# Microcontroller.net
KiCad netlist of a schematic drawn in Altium Designer
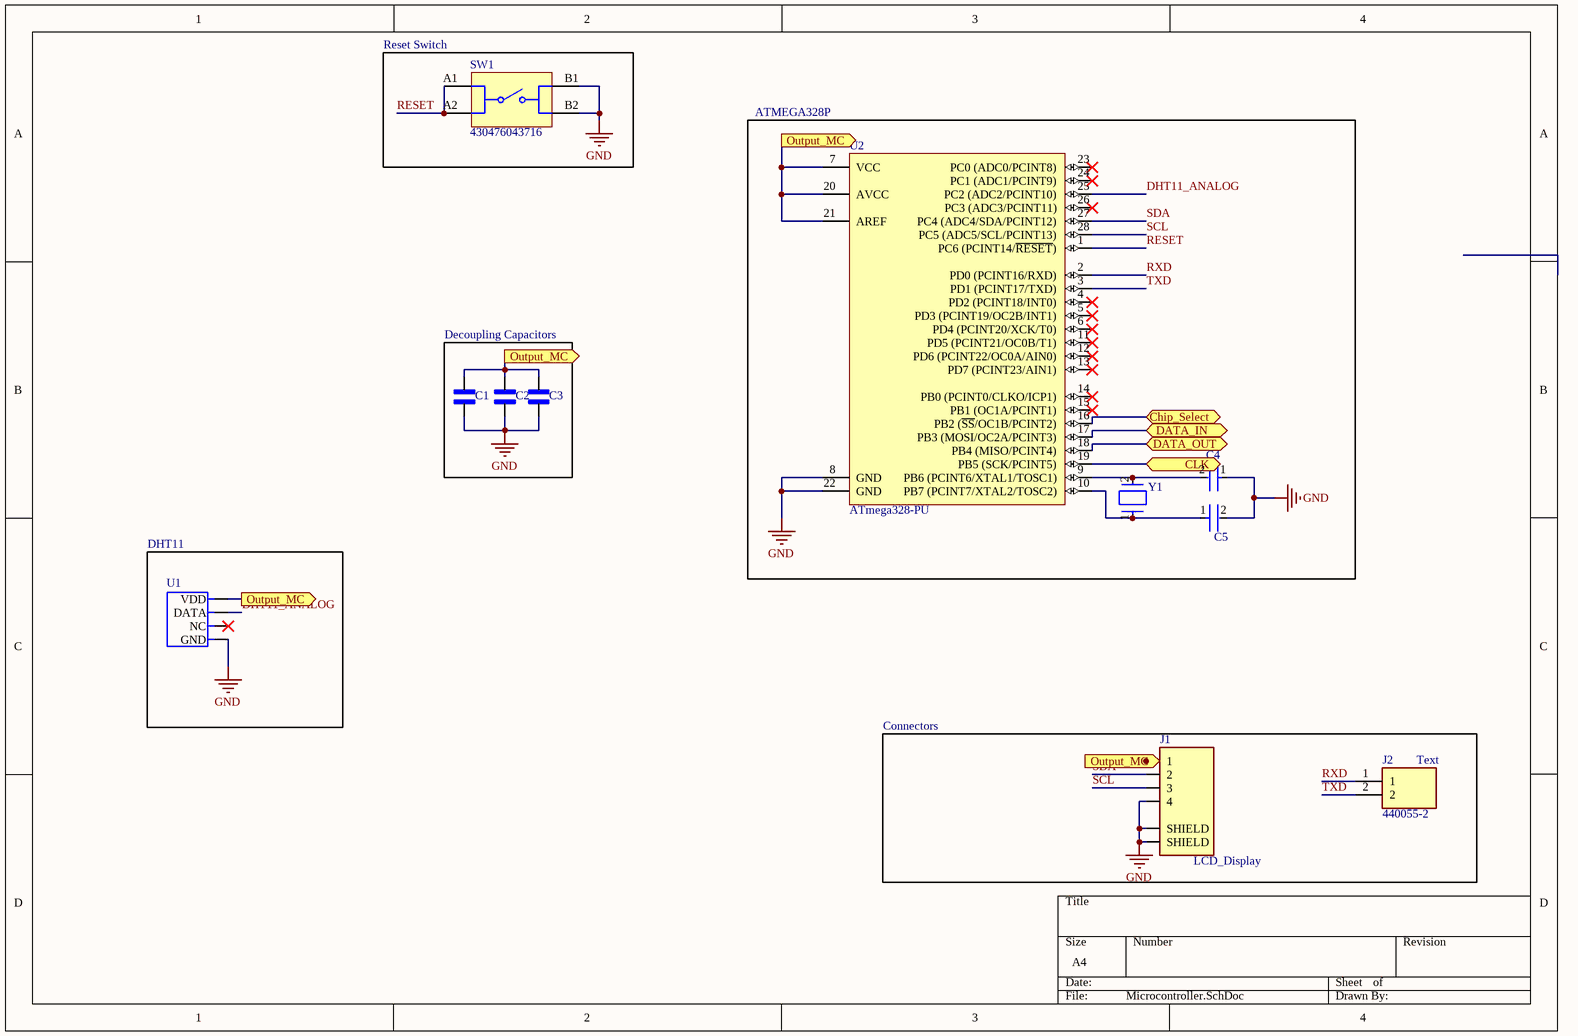
[diagram p0: Microcontroller.SchDoc]

(export (version "E")
  (design (tool "Eeschema 10.0.6"))
  (components
    (comp (ref "C1")
      (value "GRM033C71C104ME14D")
      (footprint "CAPC0603X33N")
      (description "Cap Ceramic 0.1uF 16V X7S 20% Pad SMD 0201 125C T/R")
      (fields (field (name "MF") "{'manufacturer': u'Murata'}"))
      (libsource (lib "SnapEDA_Library") (part "GRM033C71C104ME14D"))
    )
    (comp (ref "C2")
      (value "GRM033C71C104ME14D")
      (footprint "CAPC0603X33N")
      (description "Cap Ceramic 0.1uF 16V X7S 20% Pad SMD 0201 125C T/R")
      (fields (field (name "MF") "{'manufacturer': u'Murata'}"))
      (libsource (lib "SnapEDA_Library") (part "GRM033C71C104ME14D"))
    )
    (comp (ref "C3")
      (value "GRM033C71C104ME14D")
      (footprint "CAPC0603X33N")
      (description "Cap Ceramic 0.1uF 16V X7S 20% Pad SMD 0201 125C T/R")
      (fields (field (name "MF") "{'manufacturer': u'Murata'}"))
      (libsource (lib "SnapEDA_Library") (part "GRM033C71C104ME14D"))
    )
    (comp (ref "C4")
      (value "C0603X104K5RACTU")
      (footprint "FP-C0603-CJ-MFG")
      (description "CAP CER 0.1UF 50V X7R 0603")
      (fields (field (name "VOLTAGE") "50V") (field (name "MANUFACTURER") "Kemet"))
      (libsource (lib "Altium Content Vault") (part "11868f565c42a9108669ba33697ecf6"))
    )
    (comp (ref "C5")
      (value "C0603X104K5RACTU")
      (footprint "FP-C0603-CJ-MFG")
      (description "CAP CER 0.1UF 50V X7R 0603")
      (fields (field (name "VOLTAGE") "50V") (field (name "MANUFACTURER") "Kemet"))
      (libsource (lib "Altium Content Vault") (part "11868f565c42a9108669ba33697ecf6"))
    )
    (comp (ref "J1")
      (value "SM04B-SRSS-TB(LF)(SN)")
      (footprint "JST_SM04B-SRSS-TB(LF)(SN)")
      (description "SH Series 1.0 mm Pitch 2 Position Single Row Side Entry Shrouded Header")
      (fields (field (name "MF") "{'manufacturer': u'JST Sales'}"))
      (libsource (lib "SnapEDA_Library") (part "SM04B-SRSS-TB(LF)(SN)"))
    )
    (comp (ref "J2")
      (value "440055-2")
      (footprint "TE_440055-2")
      (fields (field (name "MF") "{'manufacturer': u'TE Connectivity'}"))
      (libsource (lib "SnapEDA_Library") (part "440055-2"))
    )
    (comp (ref "SW1")
      (value "430476043716")
      (footprint "4304x60437x6")
      (libsource (lib "Altium Content Vault") (part "SPST-NO_4P"))
    )
    (comp (ref "U1")
      (value "TEM-HUM-DHT11(4P-15.5X12.0MM)")
      (footprint "SNR4-2.54-15.5X12.0X5.5MM")
      (description "314010000")
      (fields
        (field (name "MF") "{'manufacturer': u'UNIVERSAL-SOLDER Electronics Ltd'}")
        (field (name "MP") "DHT11")
      )
      (libsource (lib "SnapEDA_Library") (part "TEM-HUM-DHT11(4P-15.5X12.0MM)"))
    )
    (comp (ref "U2")
      (value "ATmega328-PU")
      (footprint "28P3")
      (libsource (lib "Altium Content Vault") (part "MC-8B-ATM48-IL28"))
    )
    (comp (ref "Y1")
      (value "ABM3-8.000MHZ-D2Y-T")
      (footprint "FP-ABM3-MFG")
      (description "Crystal 8MHz ±20ppm 18pF SMD-2 5mm x 3.2mm")
      (fields (field (name "TOLERANCE") "20ppm"))
      (libsource (lib "Altium Content Vault") (part "c23a69dc6c9e2f18f2079038eb95dd1"))
    )
  )
  (nets
    (net (code "1") (name "/CLK") (class "Default")
      (node (ref "U2") (pin "19") (pinfunction "PB5_(SCK/PCINT5)_19") (pintype "bidirectional"))
    )
    (net (code "2") (name "/Chip_Select") (class "Default")
      (node (ref "U2") (pin "16") (pinfunction "PB2_(~{SS}/OC1B/PCINT2)_16") (pintype "bidirectional"))
    )
    (net (code "3") (name "/DATA_IN") (class "Default")
      (node (ref "U2") (pin "17") (pinfunction "PB3_(MOSI/OC2A/PCINT3)_17") (pintype "bidirectional"))
    )
    (net (code "4") (name "/DATA_OUT") (class "Default")
      (node (ref "U2") (pin "18") (pinfunction "PB4_(MISO/PCINT4)_18") (pintype "bidirectional"))
    )
    (net (code "5") (name "/DHT11_ANALOG") (class "Default")
      (node (ref "U1") (pin "2") (pinfunction "DATA_2") (pintype "bidirectional"))
      (node (ref "U2") (pin "25") (pinfunction "PC2_(ADC2/PCINT10)_25") (pintype "bidirectional"))
    )
    (net (code "6") (name "/Output_MC") (class "Default")
      (node (ref "C1") (pin "2") (pinfunction "2_2") (pintype "passive"))
      (node (ref "C2") (pin "2") (pinfunction "2_2") (pintype "passive"))
      (node (ref "C3") (pin "2") (pinfunction "2_2") (pintype "passive"))
      (node (ref "J1") (pin "1") (pinfunction "1_1") (pintype "passive"))
      (node (ref "U1") (pin "1") (pinfunction "VDD_1") (pintype "power_in"))
      (node (ref "U2") (pin "20") (pinfunction "AVCC_20") (pintype "power_in"))
      (node (ref "U2") (pin "21") (pinfunction "AREF_21") (pintype "power_in"))
      (node (ref "U2") (pin "7") (pinfunction "VCC_7") (pintype "power_in"))
    )
    (net (code "7") (name "/RESET") (class "Default")
      (node (ref "SW1") (pin "A1") (pinfunction "A1_A1") (pintype "passive"))
      (node (ref "SW1") (pin "A2") (pinfunction "A2_A2") (pintype "passive"))
      (node (ref "U2") (pin "1") (pinfunction "PC6_(PCINT14/~{RESET})_1") (pintype "bidirectional"))
    )
    (net (code "8") (name "/RXD") (class "Default")
      (node (ref "J2") (pin "1") (pinfunction "1_1") (pintype "passive"))
      (node (ref "U2") (pin "2") (pinfunction "PD0_(PCINT16/RXD)_2") (pintype "bidirectional"))
    )
    (net (code "9") (name "/SCL") (class "Default")
      (node (ref "J1") (pin "3") (pinfunction "3_3") (pintype "passive"))
      (node (ref "U2") (pin "28") (pinfunction "PC5_(ADC5/SCL/PCINT13)_28") (pintype "bidirectional"))
    )
    (net (code "10") (name "/SDA") (class "Default")
      (node (ref "J1") (pin "2") (pinfunction "2_2") (pintype "passive"))
      (node (ref "U2") (pin "27") (pinfunction "PC4_(ADC4/SDA/PCINT12)_27") (pintype "bidirectional"))
    )
    (net (code "11") (name "/TXD") (class "Default")
      (node (ref "J2") (pin "2") (pinfunction "2_2") (pintype "passive"))
      (node (ref "U2") (pin "3") (pinfunction "PD1_(PCINT17/TXD)_3") (pintype "bidirectional"))
    )
    (net (code "12") (name "GND") (class "Default")
      (node (ref "C1") (pin "1") (pinfunction "1_1") (pintype "passive"))
      (node (ref "C2") (pin "1") (pinfunction "1_1") (pintype "passive"))
      (node (ref "C3") (pin "1") (pinfunction "1_1") (pintype "passive"))
      (node (ref "C4") (pin "1") (pinfunction "1_1") (pintype "passive"))
      (node (ref "C5") (pin "2") (pinfunction "2_2") (pintype "passive"))
      (node (ref "J1") (pin "4") (pinfunction "4_4") (pintype "passive"))
      (node (ref "J1") (pin "S1") (pinfunction "SHIELD_S1") (pintype "passive"))
      (node (ref "J1") (pin "S2") (pinfunction "SHIELD_S2") (pintype "passive"))
      (node (ref "SW1") (pin "B1") (pinfunction "B1_B1") (pintype "passive"))
      (node (ref "SW1") (pin "B2") (pinfunction "B2_B2") (pintype "passive"))
      (node (ref "U1") (pin "4") (pinfunction "GND_4") (pintype "power_in"))
      (node (ref "U2") (pin "22") (pinfunction "GND_22") (pintype "power_in"))
      (node (ref "U2") (pin "8") (pinfunction "GND_8") (pintype "power_in"))
    )
    (net (code "13") (name "Net-(U2-PB6_(PCINT6{slash}XTAL1{slash}TOSC1))") (class "Default")
      (node (ref "C4") (pin "2") (pinfunction "2_2") (pintype "passive"))
      (node (ref "U2") (pin "9") (pinfunction "PB6_(PCINT6/XTAL1/TOSC1)_9") (pintype "bidirectional"))
      (node (ref "Y1") (pin "2") (pinfunction "2_2") (pintype "passive"))
    )
    (net (code "14") (name "Net-(U2-PB7_(PCINT7{slash}XTAL2{slash}TOSC2))") (class "Default")
      (node (ref "C5") (pin "1") (pinfunction "1_1") (pintype "passive"))
      (node (ref "U2") (pin "10") (pinfunction "PB7_(PCINT7/XTAL2/TOSC2)_10") (pintype "bidirectional"))
      (node (ref "Y1") (pin "1") (pinfunction "1_1") (pintype "passive"))
    )
    (net (code "15") (name "unconnected-(U1-NC-Pad3)") (class "Default")
      (node (ref "U1") (pin "3") (pinfunction "NC_3") (pintype "passive+no_connect"))
    )
    (net (code "16") (name "unconnected-(U2-PB0_(PCINT0{slash}CLKO{slash}ICP1)-Pad14)") (class "Default")
      (node (ref "U2") (pin "14") (pinfunction "PB0_(PCINT0/CLKO/ICP1)_14") (pintype "bidirectional+no_connect"))
    )
    (net (code "17") (name "unconnected-(U2-PB1_(OC1A{slash}PCINT1)-Pad15)") (class "Default")
      (node (ref "U2") (pin "15") (pinfunction "PB1_(OC1A/PCINT1)_15") (pintype "bidirectional+no_connect"))
    )
    (net (code "18") (name "unconnected-(U2-PC0_(ADC0{slash}PCINT8)-Pad23)") (class "Default")
      (node (ref "U2") (pin "23") (pinfunction "PC0_(ADC0/PCINT8)_23") (pintype "bidirectional+no_connect"))
    )
    (net (code "19") (name "unconnected-(U2-PC1_(ADC1{slash}PCINT9)-Pad24)") (class "Default")
      (node (ref "U2") (pin "24") (pinfunction "PC1_(ADC1/PCINT9)_24") (pintype "bidirectional+no_connect"))
    )
    (net (code "20") (name "unconnected-(U2-PC3_(ADC3{slash}PCINT11)-Pad26)") (class "Default")
      (node (ref "U2") (pin "26") (pinfunction "PC3_(ADC3/PCINT11)_26") (pintype "bidirectional+no_connect"))
    )
    (net (code "21") (name "unconnected-(U2-PD2_(PCINT18{slash}INT0)-Pad4)") (class "Default")
      (node (ref "U2") (pin "4") (pinfunction "PD2_(PCINT18/INT0)_4") (pintype "bidirectional+no_connect"))
    )
    (net (code "22") (name "unconnected-(U2-PD3_(PCINT19{slash}OC2B{slash}INT1)-Pad5)") (class "Default")
      (node (ref "U2") (pin "5") (pinfunction "PD3_(PCINT19/OC2B/INT1)_5") (pintype "bidirectional+no_connect"))
    )
    (net (code "23") (name "unconnected-(U2-PD4_(PCINT20{slash}XCK{slash}T0)-Pad6)") (class "Default")
      (node (ref "U2") (pin "6") (pinfunction "PD4_(PCINT20/XCK/T0)_6") (pintype "bidirectional+no_connect"))
    )
    (net (code "24") (name "unconnected-(U2-PD5_(PCINT21{slash}OC0B{slash}T1)-Pad11)") (class "Default")
      (node (ref "U2") (pin "11") (pinfunction "PD5_(PCINT21/OC0B/T1)_11") (pintype "bidirectional+no_connect"))
    )
    (net (code "25") (name "unconnected-(U2-PD6_(PCINT22{slash}OC0A{slash}AIN0)-Pad12)") (class "Default")
      (node (ref "U2") (pin "12") (pinfunction "PD6_(PCINT22/OC0A/AIN0)_12") (pintype "bidirectional+no_connect"))
    )
    (net (code "26") (name "unconnected-(U2-PD7_(PCINT23{slash}AIN1)-Pad13)") (class "Default")
      (node (ref "U2") (pin "13") (pinfunction "PD7_(PCINT23/AIN1)_13") (pintype "bidirectional+no_connect"))
    )
  )
)
